# imu_ism330.net
KiCad netlist of a schematic drawn in Altium Designer
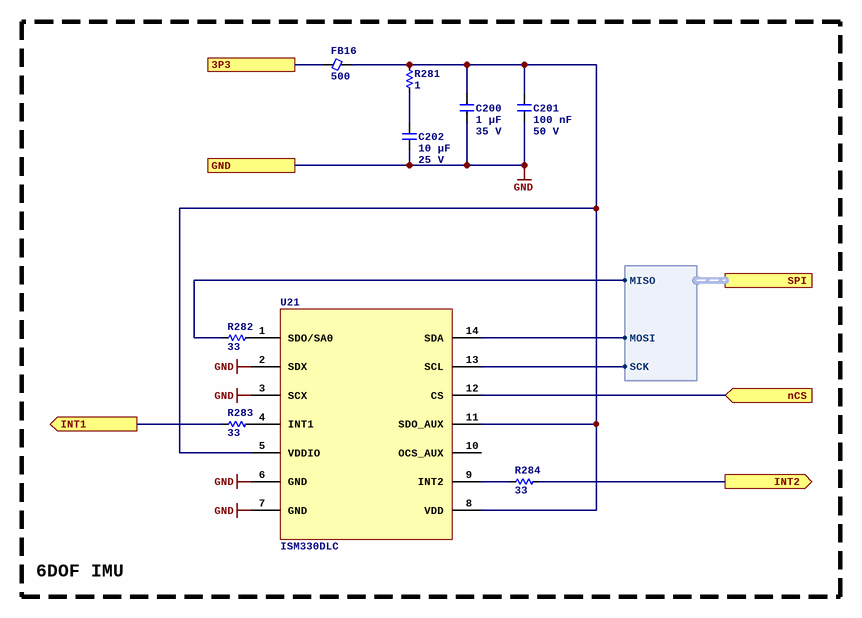
[diagram p0: imu_ism330.SchDoc]

(export (version "E")
  (design (tool "Eeschema 10.0.6"))
  (components
    (comp (ref "C200")
      (value "GMK107AB7105KAHT")
      (footprint "C0603")
      (fields
        (field (name "CAPACITANCE") "1 µF")
        (field (name "MANUFACTURER") "Taiyo Yuden")
        (field (name "VOLTAGE RATING") "35 V")
      )
      (libsource (lib "database") (part "__template_cap"))
    )
    (comp (ref "C201")
      (value "CL05B104KB54PNC")
      (footprint "C0402")
      (fields
        (field (name "CAPACITANCE") "100 nF")
        (field (name "MANUFACTURER") "Samsung Electro-Mechanics")
        (field (name "VOLTAGE RATING") "50 V")
      )
      (libsource (lib "database") (part "__template_cap"))
    )
    (comp (ref "C202")
      (value "CL21B106KAYQNNE")
      (footprint "C0805")
      (fields
        (field (name "CAPACITANCE") "10 µF")
        (field (name "MANUFACTURER") "Samsung Electro-Mechanics")
        (field (name "VOLTAGE RATING") "25 V")
      )
      (libsource (lib "database") (part "__template_cap"))
    )
    (comp (ref "FB16")
      (value "BLM15AX601SN1D")
      (footprint "FB0402")
      (fields (field (name "MANUFACTURER") "Murata Electronics") (field (name "CURRENT RATING (MA)") "500"))
      (libsource (lib "database") (part "__template_fb"))
    )
    (comp (ref "R281")
      (value "1")
      (footprint "R0402")
      (fields
        (field (name "TOLERANCE") "1%")
        (field (name "MANUFACTURER PART NUMBER") "CRCW04021R00FKED")
        (field (name "MANUFACTURER") "Vishay Intertech")
      )
      (libsource (lib "database") (part "__template_resistor"))
    )
    (comp (ref "R282")
      (value "33")
      (footprint "R0402")
      (fields
        (field (name "TOLERANCE") "1%")
        (field (name "MANUFACTURER PART NUMBER") "0402WGF330JTCE")
        (field (name "MANUFACTURER") "UNI-ROYAL(Uniroyal Elec)")
      )
      (libsource (lib "database") (part "__template_resistor"))
    )
    (comp (ref "R283")
      (value "33")
      (footprint "R0402")
      (fields
        (field (name "TOLERANCE") "1%")
        (field (name "MANUFACTURER PART NUMBER") "0402WGF330JTCE")
        (field (name "MANUFACTURER") "UNI-ROYAL(Uniroyal Elec)")
      )
      (libsource (lib "database") (part "__template_resistor"))
    )
    (comp (ref "R284")
      (value "33")
      (footprint "R0402")
      (fields
        (field (name "TOLERANCE") "1%")
        (field (name "MANUFACTURER PART NUMBER") "0402WGF330JTCE")
        (field (name "MANUFACTURER") "UNI-ROYAL(Uniroyal Elec)")
      )
      (libsource (lib "database") (part "__template_resistor"))
    )
    (comp (ref "U21")
      (value "ISM330DLC")
      (footprint "ST_LGA-14L")
      (description "ST ACCELEROMETER/GYROSCOPE 3D 14LGA LOW POWER")
      (fields
        (field (name "MANUFACTURER PART NUMBER") "ISM330DLC")
        (field (name "MANUFACTURER") "ST Microelectronics")
      )
      (libsource (lib "database") (part "ISM330DLC"))
    )
  )
  (nets
    (net (code "2") (name "/3P3") (class "Default") (node (ref "FB16") (pin "1") (pintype "passive")))
    (net (code "3") (name "/INT1") (class "Default") (node (ref "R283") (pin "1") (pintype "passive")))
    (net (code "4") (name "/INT2") (class "Default") (node (ref "R284") (pin "2") (pintype "passive")))
    (net (code "5") (name "/MISO") (class "Default") (node (ref "R282") (pin "1") (pintype "passive")))
    (net (code "6") (name "/MOSI") (class "Default")
      (node (ref "U21") (pin "14") (pinfunction "SDA_14") (pintype "passive"))
    )
    (net (code "7") (name "/SCK") (class "Default")
      (node (ref "U21") (pin "13") (pinfunction "SCL_13") (pintype "passive"))
    )
    (net (code "8") (name "/nCS") (class "Default")
      (node (ref "U21") (pin "12") (pinfunction "CS_12") (pintype "passive"))
    )
    (net (code "10") (name "GND") (class "Default")
      (node (ref "C200") (pin "2") (pintype "passive"))
      (node (ref "C201") (pin "2") (pintype "passive"))
      (node (ref "C202") (pin "2") (pintype "passive"))
      (node (ref "U21") (pin "2") (pinfunction "SDX_2") (pintype "passive"))
      (node (ref "U21") (pin "3") (pinfunction "SCX_3") (pintype "passive"))
      (node (ref "U21") (pin "6") (pinfunction "GND_6") (pintype "passive"))
      (node (ref "U21") (pin "7") (pinfunction "GND_7") (pintype "passive"))
    )
    (net (code "11") (name "Net-(C202-Pad1)") (class "Default")
      (node (ref "C202") (pin "1") (pintype "passive"))
      (node (ref "R281") (pin "1") (pintype "passive"))
    )
    (net (code "12") (name "Net-(U21-INT1)") (class "Default")
      (node (ref "R283") (pin "2") (pintype "passive"))
      (node (ref "U21") (pin "4") (pinfunction "INT1_4") (pintype "passive"))
    )
    (net (code "13") (name "Net-(U21-INT2)") (class "Default")
      (node (ref "R284") (pin "1") (pintype "passive"))
      (node (ref "U21") (pin "9") (pinfunction "INT2_9") (pintype "passive"))
    )
    (net (code "14") (name "Net-(U21-SDO_AUX)") (class "Default")
      (node (ref "C200") (pin "1") (pintype "passive"))
      (node (ref "C201") (pin "1") (pintype "passive"))
      (node (ref "FB16") (pin "2") (pintype "passive"))
      (node (ref "R281") (pin "2") (pintype "passive"))
      (node (ref "U21") (pin "11") (pinfunction "SDO_AUX_11") (pintype "passive"))
      (node (ref "U21") (pin "5") (pinfunction "VDDIO_5") (pintype "passive"))
      (node (ref "U21") (pin "8") (pinfunction "VDD_8") (pintype "passive"))
    )
    (net (code "15") (name "Net-(U21-SDO{slash}SA0)") (class "Default")
      (node (ref "R282") (pin "2") (pintype "passive"))
      (node (ref "U21") (pin "1") (pinfunction "SDO/SA0_1") (pintype "passive"))
    )
    (net (code "16") (name "unconnected-(U21-OCS_AUX-Pad10)") (class "Default")
      (node (ref "U21") (pin "10") (pinfunction "OCS_AUX_10") (pintype "passive"))
    )
  )
)
